# 1_AT_Link_EZ_V1_2.net
KiCad netlist of a schematic drawn in Altium Designer
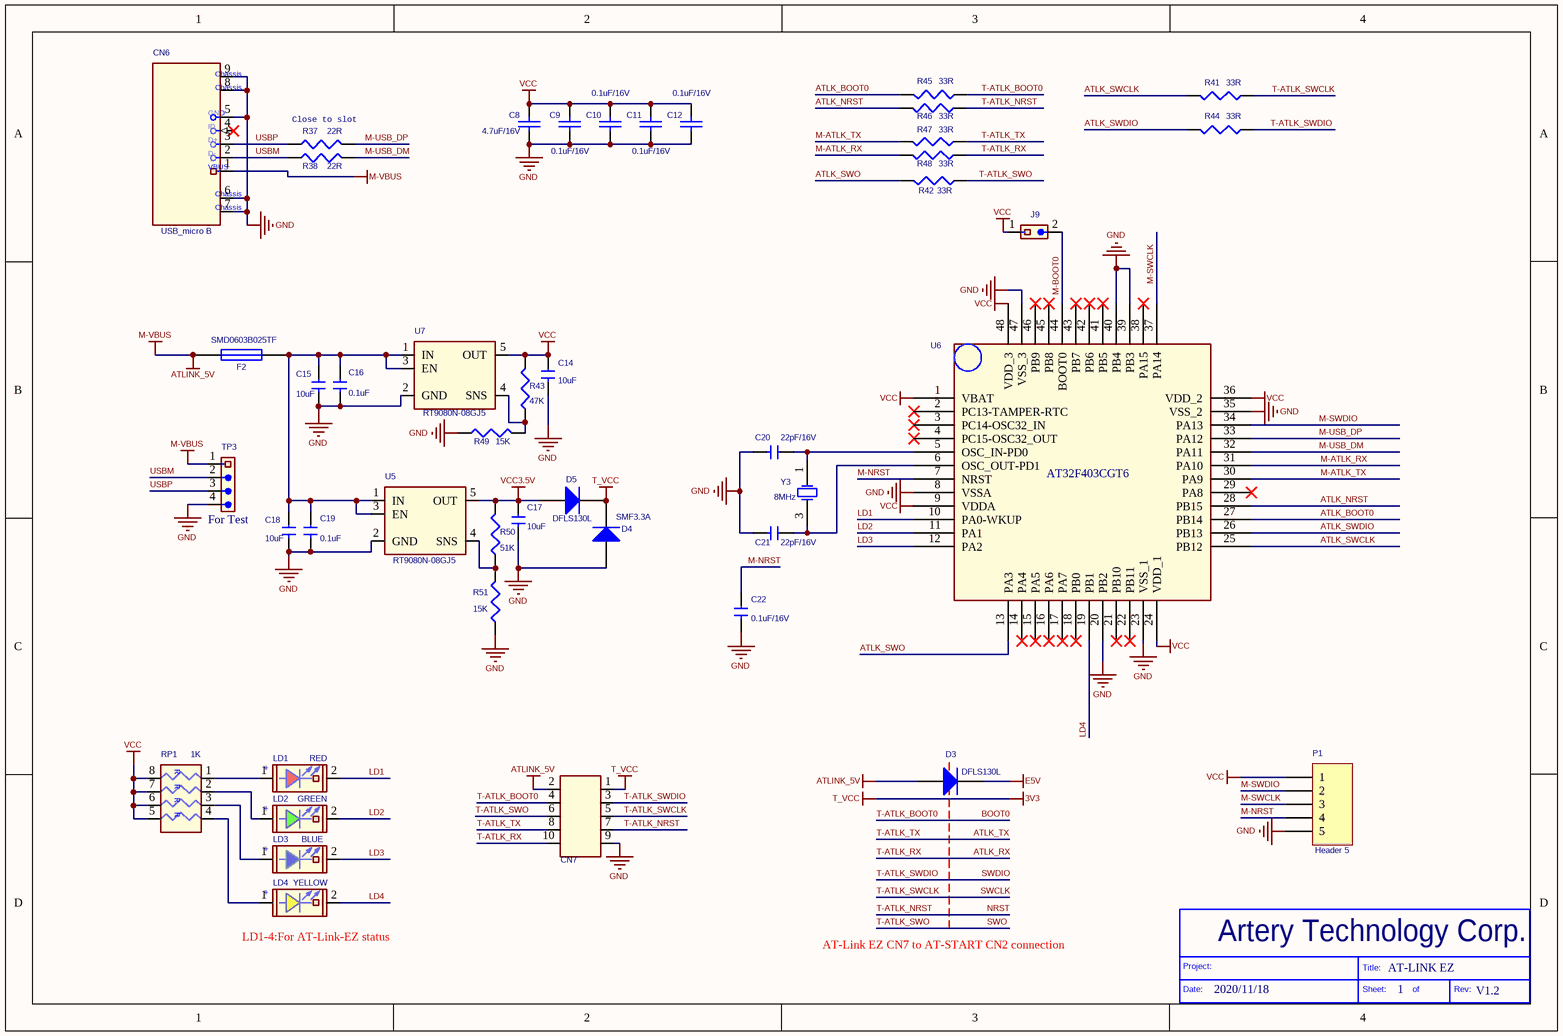
[diagram p0: 1_AT_Link_EZ_V1.2.SchDoc]

(export (version "E")
  (design (tool "Eeschema 10.0.6"))
  (components
    (comp (ref "C8")
      (value "4.7uF/16V")
      (footprint "C0603")
      (description "Capacitor (Semiconductor SIM Model)")
      (fields (field (name "PUBLISHER") "Altium Limited"))
      (libsource (lib "PcbLib") (part "Cap Semi"))
    )
    (comp (ref "C9")
      (value "0.1uF/16V")
      (footprint "C0603")
      (description "Capacitor (Semiconductor SIM Model)")
      (fields (field (name "PUBLISHER") "Altium Limited"))
      (libsource (lib "PcbLib") (part "Cap Semi"))
    )
    (comp (ref "C10")
      (value "0.1uF/16V")
      (footprint "C0603")
      (description "Capacitor (Semiconductor SIM Model)")
      (fields (field (name "PUBLISHER") "Altium Limited"))
      (libsource (lib "PcbLib") (part "Cap Semi"))
    )
    (comp (ref "C11")
      (value "0.1uF/16V")
      (footprint "C0603")
      (description "Capacitor (Semiconductor SIM Model)")
      (fields (field (name "PUBLISHER") "Altium Limited"))
      (libsource (lib "PcbLib") (part "Cap Semi"))
    )
    (comp (ref "C12")
      (value "0.1uF/16V")
      (footprint "C0603")
      (description "Capacitor (Semiconductor SIM Model)")
      (fields (field (name "PUBLISHER") "Altium Limited"))
      (libsource (lib "PcbLib") (part "Cap Semi"))
    )
    (comp (ref "C14") (value "10uF") (libsource (lib "*") (part "0.1uF,50V,20%,SMD0603")))
    (comp (ref "C15") (value "10uF") (libsource (lib "*") (part "0.1uF,50V,20%,SMD0603")))
    (comp (ref "C16") (value "0.1uF") (libsource (lib "*") (part "0.1uF,50V,20%,SMD0603")))
    (comp (ref "C17") (value "10uF") (libsource (lib "*") (part "0.1uF,50V,20%,SMD0603")))
    (comp (ref "C18") (value "10uF") (libsource (lib "*") (part "0.1uF,50V,20%,SMD0603")))
    (comp (ref "C19") (value "0.1uF") (libsource (lib "*") (part "0.1uF,50V,20%,SMD0603")))
    (comp (ref "C20") (value "22pF/16V") (libsource (lib "*") (part "10pF,50V,5%,SMD0603")))
    (comp (ref "C21") (value "22pF/16V") (libsource (lib "*") (part "10pF,50V,5%,SMD0603")))
    (comp (ref "C22") (value "0.1uF/16V") (libsource (lib "*") (part "0.1uF,50V,20%,SMD0603")))
    (comp (ref "CN6") (value "USB_micro B") (libsource (lib "*") (part "USB_miniAB,SMD_0")))
    (comp (ref "CN7") (value "CON1") (footprint "HDR2X5") (libsource (lib "*") (part "CON10A_0")))
    (comp (ref "D3")
      (value "DFLS130L")
      (footprint "SOD-123")
      (description "Default Diode")
      (fields (field (name "PUBLISHER") "Altium Limited"))
      (libsource (lib "Miscellaneous Devices") (part "Diode"))
    )
    (comp (ref "D4")
      (value "SMF3.3A")
      (footprint "SOD-123")
      (description "Default Diode")
      (fields (field (name "PUBLISHER") "Altium Limited"))
      (libsource (lib "Miscellaneous Devices") (part "Diode"))
    )
    (comp (ref "D5")
      (value "DFLS130L")
      (footprint "SOD-123")
      (description "Default Diode")
      (fields (field (name "PUBLISHER") "Altium Limited"))
      (libsource (lib "Miscellaneous Devices") (part "Diode"))
    )
    (comp (ref "F2")
      (value "SMD0603B025TF")
      (footprint "r0603")
      (description "Fuse")
      (fields (field (name "PUBLISHER") "Altium Limited"))
      (libsource (lib "Miscellaneous Devices") (part "Fuse 1"))
    )
    (comp (ref "J9")
      (value "1X2P_2.54M")
      (footprint "HDR1X2")
      (libsource (lib "*") (part "1X2P,Male,DIP_2.54"))
    )
    (comp (ref "LD1")
      (value "RED")
      (footprint "LED0603")
      (libsource (lib "AT32F403_TINY_LQFP144_Library") (part "RED,SMD0603"))
    )
    (comp (ref "LD2")
      (value "GREEN")
      (footprint "LED0603")
      (libsource (lib "AT32F403_TINY_LQFP144_Library") (part "GREEN,SMD0603"))
    )
    (comp (ref "LD3")
      (value "BLUE")
      (footprint "LED0603")
      (description "贴片LED 蓝色 0603")
      (libsource (lib "AT_START_F415") (part "BLUE,SMD0603"))
    )
    (comp (ref "LD4")
      (value "YELLOW")
      (footprint "LED0603")
      (libsource (lib "Schlib1") (part "YELLOW,SMD0603"))
    )
    (comp (ref "P1")
      (value "Header 5")
      (footprint "HDR1X5")
      (description "Header, 5-Pin")
      (fields (field (name "PUBLISHER") "Altium Limited"))
      (libsource (lib "Miscellaneous Connectors") (part "Header 5"))
    )
    (comp (ref "R37") (value "22R") (libsource (lib "*") (part "22,1/10W,1%,SMD0603")))
    (comp (ref "R38") (value "22R") (libsource (lib "*") (part "22,1/10W,1%,SMD0603")))
    (comp (ref "R41") (value "33R") (libsource (lib "*") (part "22,1/10W,1%,SMD0603")))
    (comp (ref "R42")
      (value "33R")
      (description "贴片电阻33R,1/10W,5%,0603")
      (libsource (lib "*") (part "22,1/10W,1%,SMD0603"))
    )
    (comp (ref "R43") (value "47K") (libsource (lib "*") (part "470,1/10W,1%,SMD0603")))
    (comp (ref "R44") (value "33R") (libsource (lib "*") (part "22,1/10W,1%,SMD0603")))
    (comp (ref "R45") (value "33R") (libsource (lib "*") (part "22,1/10W,1%,SMD0603")))
    (comp (ref "R46") (value "33R") (libsource (lib "*") (part "22,1/10W,1%,SMD0603")))
    (comp (ref "R47") (value "33R") (libsource (lib "*") (part "22,1/10W,1%,SMD0603")))
    (comp (ref "R48") (value "33R") (libsource (lib "*") (part "22,1/10W,1%,SMD0603")))
    (comp (ref "R49") (value "15K") (libsource (lib "*") (part "470,1/10W,1%,SMD0603")))
    (comp (ref "R50") (value "51K") (libsource (lib "*") (part "470,1/10W,1%,SMD0603")))
    (comp (ref "R51") (value "15K") (libsource (lib "*") (part "470,1/10W,1%,SMD0603")))
    (comp (ref "RP1") (value "1K") (libsource (lib "*") (part "22,1/16W,5%,8P4R")))
    (comp (ref "TP3")
      (value "1X4P_2.54F")
      (footprint "HDR1X4 - top")
      (libsource (lib "*") (part "1X4P,Female,DIP_2.54"))
    )
    (comp (ref "U5") (value "RT9080N-08GJ5") (libsource (lib "SCM_START_402F") (part "RT9080N")))
    (comp (ref "U6")
      (value "AT32F403CGT6")
      (footprint "AT403-ALL-PcbLib:LQFP48 - 2")
      (libsource (lib "AT403-ALL-Package") (part "LQFP48&QFN48"))
    )
    (comp (ref "U7") (value "RT9080N-08GJ5") (libsource (lib "SCM_START_402F") (part "RT9080N")))
    (comp (ref "Y3")
      (value "8MHz")
      (footprint "SMD_5032_4P")
      (description "?片晶振")
      (libsource (lib "Artery_Wanbing") (part "SMD-5032_4P  8MHZ 20PF 10PPM"))
    )
  )
  (nets
    (net (code "1") (name "/ATLK_BOOT0") (class "Default")
      (node (ref "R45") (pin "2") (pinfunction "2_2") (pintype "passive"))
      (node (ref "U6") (pin "27") (pinfunction "PB14_27") (pintype "passive"))
    )
    (net (code "2") (name "/ATLK_NRST") (class "Default")
      (node (ref "R46") (pin "2") (pinfunction "2_2") (pintype "passive"))
      (node (ref "U6") (pin "28") (pinfunction "PB15_28") (pintype "passive"))
    )
    (net (code "3") (name "/ATLK_RX") (class "Default")
      (node (ref "CN7") (pin "10") (pinfunction "10_10") (pintype "passive"))
      (node (ref "R48") (pin "1") (pinfunction "1_1") (pintype "passive"))
    )
    (net (code "4") (name "/ATLK_SWCLK") (class "Default")
      (node (ref "R41") (pin "2") (pinfunction "2_2") (pintype "passive"))
      (node (ref "U6") (pin "25") (pinfunction "PB12_25") (pintype "passive"))
    )
    (net (code "5") (name "/ATLK_SWDIO") (class "Default")
      (node (ref "R44") (pin "2") (pinfunction "2_2") (pintype "passive"))
      (node (ref "U6") (pin "26") (pinfunction "PB13_26") (pintype "passive"))
    )
    (net (code "6") (name "/ATLK_SWO") (class "Default")
      (node (ref "R42") (pin "2") (pinfunction "2_2") (pintype "passive"))
      (node (ref "U6") (pin "13") (pinfunction "PA3_13") (pintype "passive"))
    )
    (net (code "7") (name "/ATLK_TX") (class "Default")
      (node (ref "CN7") (pin "8") (pinfunction "8_8") (pintype "passive"))
      (node (ref "R47") (pin "1") (pinfunction "1_1") (pintype "passive"))
    )
    (net (code "8") (name "/BOOT0") (class "Default")
      (node (ref "CN7") (pin "4") (pinfunction "4_4") (pintype "passive"))
      (node (ref "R45") (pin "1") (pinfunction "1_1") (pintype "passive"))
    )
    (net (code "9") (name "/LD1") (class "Default")
      (node (ref "LD1") (pin "2") (pinfunction "CATHODE_2") (pintype "passive"))
      (node (ref "U6") (pin "10") (pinfunction "PA0-WKUP_10") (pintype "passive"))
    )
    (net (code "10") (name "/LD2") (class "Default")
      (node (ref "LD2") (pin "2") (pinfunction "CATHODE_2") (pintype "passive"))
      (node (ref "U6") (pin "11") (pinfunction "PA1_11") (pintype "passive"))
    )
    (net (code "11") (name "/LD3") (class "Default")
      (node (ref "LD3") (pin "2") (pinfunction "CATHODE_2") (pintype "passive"))
      (node (ref "U6") (pin "12") (pinfunction "PA2_12") (pintype "passive"))
    )
    (net (code "12") (name "/LD4") (class "Default")
      (node (ref "LD4") (pin "2") (pinfunction "CATHODE_2") (pintype "passive"))
      (node (ref "U6") (pin "19") (pinfunction "PB1_19") (pintype "passive"))
    )
    (net (code "13") (name "/M-ATLK_RX") (class "Default")
      (node (ref "R48") (pin "2") (pinfunction "2_2") (pintype "passive"))
      (node (ref "U6") (pin "31") (pinfunction "PA10_31") (pintype "passive"))
    )
    (net (code "14") (name "/M-ATLK_TX") (class "Default")
      (node (ref "R47") (pin "2") (pinfunction "2_2") (pintype "passive"))
      (node (ref "U6") (pin "30") (pinfunction "PA9_30") (pintype "passive"))
    )
    (net (code "15") (name "/M-BOOT0") (class "Default")
      (node (ref "J9") (pin "2") (pinfunction "2_2") (pintype "passive"))
      (node (ref "U6") (pin "44") (pinfunction "BOOT0_44") (pintype "passive"))
    )
    (net (code "16") (name "/M-NRST") (class "Default")
      (node (ref "C22") (pin "1") (pinfunction "1_1") (pintype "passive"))
      (node (ref "P1") (pin "4") (pinfunction "4_4") (pintype "passive"))
      (node (ref "U6") (pin "7") (pinfunction "NRST_7") (pintype "passive"))
    )
    (net (code "17") (name "/M-SWCLK") (class "Default")
      (node (ref "P1") (pin "3") (pinfunction "3_3") (pintype "passive"))
      (node (ref "U6") (pin "37") (pinfunction "PA14_37") (pintype "passive"))
    )
    (net (code "18") (name "/M-SWDIO") (class "Default")
      (node (ref "P1") (pin "2") (pinfunction "2_2") (pintype "passive"))
      (node (ref "U6") (pin "34") (pinfunction "PA13_34") (pintype "passive"))
    )
    (net (code "19") (name "/M-USB_DM") (class "Default")
      (node (ref "R38") (pin "2") (pinfunction "2_2") (pintype "passive"))
      (node (ref "U6") (pin "32") (pinfunction "PA11_32") (pintype "passive"))
    )
    (net (code "20") (name "/M-USB_DP") (class "Default")
      (node (ref "R37") (pin "2") (pinfunction "2_2") (pintype "passive"))
      (node (ref "U6") (pin "33") (pinfunction "PA12_33") (pintype "passive"))
    )
    (net (code "21") (name "/NRST") (class "Default")
      (node (ref "CN7") (pin "7") (pinfunction "7_7") (pintype "passive"))
      (node (ref "R46") (pin "1") (pinfunction "1_1") (pintype "passive"))
    )
    (net (code "22") (name "/SWCLK") (class "Default")
      (node (ref "CN7") (pin "5") (pinfunction "5_5") (pintype "passive"))
      (node (ref "R41") (pin "1") (pinfunction "1_1") (pintype "passive"))
    )
    (net (code "23") (name "/SWDIO") (class "Default")
      (node (ref "CN7") (pin "3") (pinfunction "3_3") (pintype "passive"))
      (node (ref "R44") (pin "1") (pinfunction "1_1") (pintype "passive"))
    )
    (net (code "24") (name "/SWO") (class "Default")
      (node (ref "CN7") (pin "6") (pinfunction "6_6") (pintype "passive"))
      (node (ref "R42") (pin "1") (pinfunction "1_1") (pintype "passive"))
    )
    (net (code "25") (name "/USBM") (class "Default")
      (node (ref "CN6") (pin "2") (pinfunction "D-_2") (pintype "bidirectional"))
      (node (ref "R38") (pin "1") (pinfunction "1_1") (pintype "passive"))
      (node (ref "TP3") (pin "2") (pinfunction "2_2") (pintype "passive"))
    )
    (net (code "26") (name "/USBP") (class "Default")
      (node (ref "CN6") (pin "3") (pinfunction "D+_3") (pintype "bidirectional"))
      (node (ref "R37") (pin "1") (pinfunction "1_1") (pintype "passive"))
      (node (ref "TP3") (pin "3") (pinfunction "3_3") (pintype "passive"))
    )
    (net (code "27") (name "3V3") (class "Default")
      (node (ref "CN7") (pin "1") (pinfunction "1_1") (pintype "passive"))
      (node (ref "D4") (pin "2") (pinfunction "K_2") (pintype "passive"))
      (node (ref "D5") (pin "2") (pinfunction "K_2") (pintype "passive"))
    )
    (net (code "28") (name "ATLINK_5V") (class "Default")
      (node (ref "CN6") (pin "1") (pinfunction "VBUS_1") (pintype "passive"))
      (node (ref "CN7") (pin "2") (pinfunction "2_2") (pintype "passive"))
      (node (ref "D3") (pin "1") (pinfunction "A_1") (pintype "passive"))
      (node (ref "F2") (pin "1") (pinfunction "1_1") (pintype "passive"))
      (node (ref "TP3") (pin "1") (pinfunction "1_1") (pintype "passive"))
    )
    (net (code "29") (name "E5V") (class "Default")
      (node (ref "D3") (pin "2") (pinfunction "K_2") (pintype "passive"))
    )
    (net (code "30") (name "GND") (class "Default")
      (node (ref "C10") (pin "1") (pinfunction "1_1") (pintype "passive"))
      (node (ref "C11") (pin "1") (pinfunction "1_1") (pintype "passive"))
      (node (ref "C12") (pin "1") (pinfunction "1_1") (pintype "passive"))
      (node (ref "C14") (pin "2") (pinfunction "2_2") (pintype "passive"))
      (node (ref "C15") (pin "2") (pinfunction "2_2") (pintype "passive"))
      (node (ref "C16") (pin "2") (pinfunction "2_2") (pintype "passive"))
      (node (ref "C17") (pin "2") (pinfunction "2_2") (pintype "passive"))
      (node (ref "C18") (pin "2") (pinfunction "2_2") (pintype "passive"))
      (node (ref "C19") (pin "2") (pinfunction "2_2") (pintype "passive"))
      (node (ref "C20") (pin "2") (pinfunction "2_2") (pintype "passive"))
      (node (ref "C21") (pin "2") (pinfunction "2_2") (pintype "passive"))
      (node (ref "C22") (pin "2") (pinfunction "2_2") (pintype "passive"))
      (node (ref "C8") (pin "1") (pinfunction "1_1") (pintype "passive"))
      (node (ref "C9") (pin "1") (pinfunction "1_1") (pintype "passive"))
      (node (ref "CN6") (pin "5") (pinfunction "GND_5") (pintype "passive"))
      (node (ref "CN6") (pin "6") (pinfunction "6_6") (pintype "passive"))
      (node (ref "CN6") (pin "7") (pinfunction "7_7") (pintype "passive"))
      (node (ref "CN6") (pin "8") (pinfunction "8_8") (pintype "passive"))
      (node (ref "CN6") (pin "9") (pinfunction "9_9") (pintype "passive"))
      (node (ref "CN7") (pin "9") (pinfunction "9_9") (pintype "passive"))
      (node (ref "D4") (pin "1") (pinfunction "A_1") (pintype "passive"))
      (node (ref "P1") (pin "5") (pinfunction "5_5") (pintype "passive"))
      (node (ref "R49") (pin "1") (pinfunction "1_1") (pintype "passive"))
      (node (ref "R51") (pin "1") (pinfunction "1_1") (pintype "passive"))
      (node (ref "TP3") (pin "4") (pinfunction "4_4") (pintype "passive"))
      (node (ref "U5") (pin "2") (pinfunction "GND_2") (pintype "power_in"))
      (node (ref "U6") (pin "20") (pinfunction "PB2_20") (pintype "passive"))
      (node (ref "U6") (pin "23") (pinfunction "VSS_1_23") (pintype "passive"))
      (node (ref "U6") (pin "35") (pinfunction "VSS_2_35") (pintype "passive"))
      (node (ref "U6") (pin "39") (pinfunction "PB3_39") (pintype "passive"))
      (node (ref "U6") (pin "40") (pinfunction "PB4_40") (pintype "passive"))
      (node (ref "U6") (pin "47") (pinfunction "VSS_3_47") (pintype "passive"))
      (node (ref "U6") (pin "8") (pinfunction "VSSA_8") (pintype "passive"))
      (node (ref "U7") (pin "2") (pinfunction "GND_2") (pintype "power_in"))
    )
    (net (code "31") (name "Net-(LD1-ANODE)") (class "Default")
      (node (ref "LD1") (pin "1") (pinfunction "ANODE_1") (pintype "passive"))
      (node (ref "RP1") (pin "1") (pinfunction "1_1") (pintype "passive"))
    )
    (net (code "32") (name "Net-(LD2-ANODE)") (class "Default")
      (node (ref "LD2") (pin "1") (pinfunction "ANODE_1") (pintype "passive"))
      (node (ref "RP1") (pin "2") (pinfunction "2_2") (pintype "passive"))
    )
    (net (code "33") (name "Net-(LD3-ANODE)") (class "Default")
      (node (ref "LD3") (pin "1") (pinfunction "ANODE_1") (pintype "passive"))
      (node (ref "RP1") (pin "3") (pinfunction "3_3") (pintype "passive"))
    )
    (net (code "34") (name "Net-(LD4-ANODE)") (class "Default")
      (node (ref "LD4") (pin "1") (pinfunction "ANODE_1") (pintype "passive"))
      (node (ref "RP1") (pin "4") (pinfunction "4_4") (pintype "passive"))
    )
    (net (code "35") (name "Net-(U5-EN)") (class "Default")
      (node (ref "C15") (pin "1") (pinfunction "1_1") (pintype "passive"))
      (node (ref "C16") (pin "1") (pinfunction "1_1") (pintype "passive"))
      (node (ref "C18") (pin "1") (pinfunction "1_1") (pintype "passive"))
      (node (ref "C19") (pin "1") (pinfunction "1_1") (pintype "passive"))
      (node (ref "F2") (pin "2") (pinfunction "2_2") (pintype "passive"))
      (node (ref "U5") (pin "1") (pinfunction "IN_1") (pintype "power_in"))
      (node (ref "U5") (pin "3") (pinfunction "EN_3") (pintype "passive"))
      (node (ref "U7") (pin "1") (pinfunction "IN_1") (pintype "power_in"))
      (node (ref "U7") (pin "3") (pinfunction "EN_3") (pintype "passive"))
    )
    (net (code "36") (name "Net-(U5-SNS)") (class "Default")
      (node (ref "R50") (pin "1") (pinfunction "1_1") (pintype "passive"))
      (node (ref "R51") (pin "2") (pinfunction "2_2") (pintype "passive"))
      (node (ref "U5") (pin "4") (pinfunction "SNS_4") (pintype "passive"))
    )
    (net (code "37") (name "Net-(U6-OSC_IN-PD0)") (class "Default")
      (node (ref "C20") (pin "1") (pinfunction "1_1") (pintype "passive"))
      (node (ref "U6") (pin "5") (pinfunction "OSC_IN-PD0_5") (pintype "passive"))
      (node (ref "Y3") (pin "1") (pinfunction "OSC1_1") (pintype "passive"))
    )
    (net (code "38") (name "Net-(U6-OSC_OUT-PD1)") (class "Default")
      (node (ref "C21") (pin "1") (pinfunction "1_1") (pintype "passive"))
      (node (ref "U6") (pin "6") (pinfunction "OSC_OUT-PD1_6") (pintype "passive"))
      (node (ref "Y3") (pin "3") (pinfunction "OSC2_3") (pintype "passive"))
    )
    (net (code "39") (name "Net-(U7-SNS)") (class "Default")
      (node (ref "R43") (pin "1") (pinfunction "1_1") (pintype "passive"))
      (node (ref "R49") (pin "2") (pinfunction "2_2") (pintype "passive"))
      (node (ref "U7") (pin "4") (pinfunction "SNS_4") (pintype "passive"))
    )
    (net (code "40") (name "VCC") (class "Default")
      (node (ref "C10") (pin "2") (pinfunction "2_2") (pintype "passive"))
      (node (ref "C11") (pin "2") (pinfunction "2_2") (pintype "passive"))
      (node (ref "C12") (pin "2") (pinfunction "2_2") (pintype "passive"))
      (node (ref "C14") (pin "1") (pinfunction "1_1") (pintype "passive"))
      (node (ref "C8") (pin "2") (pinfunction "2_2") (pintype "passive"))
      (node (ref "C9") (pin "2") (pinfunction "2_2") (pintype "passive"))
      (node (ref "J9") (pin "1") (pinfunction "1_1") (pintype "passive"))
      (node (ref "P1") (pin "1") (pinfunction "1_1") (pintype "passive"))
      (node (ref "R43") (pin "2") (pinfunction "2_2") (pintype "passive"))
      (node (ref "RP1") (pin "5") (pinfunction "5_5") (pintype "passive"))
      (node (ref "RP1") (pin "6") (pinfunction "6_6") (pintype "passive"))
      (node (ref "RP1") (pin "7") (pinfunction "7_7") (pintype "passive"))
      (node (ref "RP1") (pin "8") (pinfunction "8_8") (pintype "passive"))
      (node (ref "U6") (pin "1") (pinfunction "VBAT_1") (pintype "passive"))
      (node (ref "U6") (pin "24") (pinfunction "VDD_1_24") (pintype "passive"))
      (node (ref "U6") (pin "36") (pinfunction "VDD_2_36") (pintype "passive"))
      (node (ref "U6") (pin "48") (pinfunction "VDD_3_48") (pintype "passive"))
      (node (ref "U6") (pin "9") (pinfunction "VDDA_9") (pintype "passive"))
      (node (ref "U7") (pin "5") (pinfunction "OUT_5") (pintype "power_in"))
    )
    (net (code "41") (name "VCC3.5V") (class "Default")
      (node (ref "C17") (pin "1") (pinfunction "1_1") (pintype "passive"))
      (node (ref "D5") (pin "1") (pinfunction "A_1") (pintype "passive"))
      (node (ref "R50") (pin "2") (pinfunction "2_2") (pintype "passive"))
      (node (ref "U5") (pin "5") (pinfunction "OUT_5") (pintype "power_in"))
    )
    (net (code "42") (name "unconnected-(CN6-ID-Pad4)") (class "Default")
      (node (ref "CN6") (pin "4") (pinfunction "ID_4") (pintype "input+no_connect"))
    )
    (net (code "43") (name "unconnected-(U6-PA4-Pad14)") (class "Default")
      (node (ref "U6") (pin "14") (pinfunction "PA4_14") (pintype "passive+no_connect"))
    )
    (net (code "44") (name "unconnected-(U6-PA5-Pad15)") (class "Default")
      (node (ref "U6") (pin "15") (pinfunction "PA5_15") (pintype "passive+no_connect"))
    )
    (net (code "45") (name "unconnected-(U6-PA6-Pad16)") (class "Default")
      (node (ref "U6") (pin "16") (pinfunction "PA6_16") (pintype "passive+no_connect"))
    )
    (net (code "46") (name "unconnected-(U6-PA7-Pad17)") (class "Default")
      (node (ref "U6") (pin "17") (pinfunction "PA7_17") (pintype "passive+no_connect"))
    )
    (net (code "47") (name "unconnected-(U6-PA8-Pad29)") (class "Default")
      (node (ref "U6") (pin "29") (pinfunction "PA8_29") (pintype "passive+no_connect"))
    )
    (net (code "48") (name "unconnected-(U6-PA15-Pad38)") (class "Default")
      (node (ref "U6") (pin "38") (pinfunction "PA15_38") (pintype "passive+no_connect"))
    )
    (net (code "49") (name "unconnected-(U6-PB0-Pad18)") (class "Default")
      (node (ref "U6") (pin "18") (pinfunction "PB0_18") (pintype "passive+no_connect"))
    )
    (net (code "50") (name "unconnected-(U6-PB5-Pad41)") (class "Default")
      (node (ref "U6") (pin "41") (pinfunction "PB5_41") (pintype "passive+no_connect"))
    )
    (net (code "51") (name "unconnected-(U6-PB6-Pad42)") (class "Default")
      (node (ref "U6") (pin "42") (pinfunction "PB6_42") (pintype "passive+no_connect"))
    )
    (net (code "52") (name "unconnected-(U6-PB7-Pad43)") (class "Default")
      (node (ref "U6") (pin "43") (pinfunction "PB7_43") (pintype "passive+no_connect"))
    )
    (net (code "53") (name "unconnected-(U6-PB8-Pad45)") (class "Default")
      (node (ref "U6") (pin "45") (pinfunction "PB8_45") (pintype "passive+no_connect"))
    )
    (net (code "54") (name "unconnected-(U6-PB9-Pad46)") (class "Default")
      (node (ref "U6") (pin "46") (pinfunction "PB9_46") (pintype "passive+no_connect"))
    )
    (net (code "55") (name "unconnected-(U6-PB10-Pad21)") (class "Default")
      (node (ref "U6") (pin "21") (pinfunction "PB10_21") (pintype "passive+no_connect"))
    )
    (net (code "56") (name "unconnected-(U6-PB11-Pad22)") (class "Default")
      (node (ref "U6") (pin "22") (pinfunction "PB11_22") (pintype "passive+no_connect"))
    )
    (net (code "57") (name "unconnected-(U6-PC13-TAMPER-RTC-Pad2)") (class "Default")
      (node (ref "U6") (pin "2") (pinfunction "PC13-TAMPER-RTC_2") (pintype "passive+no_connect"))
    )
    (net (code "58") (name "unconnected-(U6-PC14-OSC32_IN-Pad3)") (class "Default")
      (node (ref "U6") (pin "3") (pinfunction "PC14-OSC32_IN_3") (pintype "passive+no_connect"))
    )
    (net (code "59") (name "unconnected-(U6-PC15-OSC32_OUT-Pad4)") (class "Default")
      (node (ref "U6") (pin "4") (pinfunction "PC15-OSC32_OUT_4") (pintype "passive+no_connect"))
    )
  )
)
